# Blend_V2_0_20170309.net
KiCad netlist of a schematic drawn in EAGLE
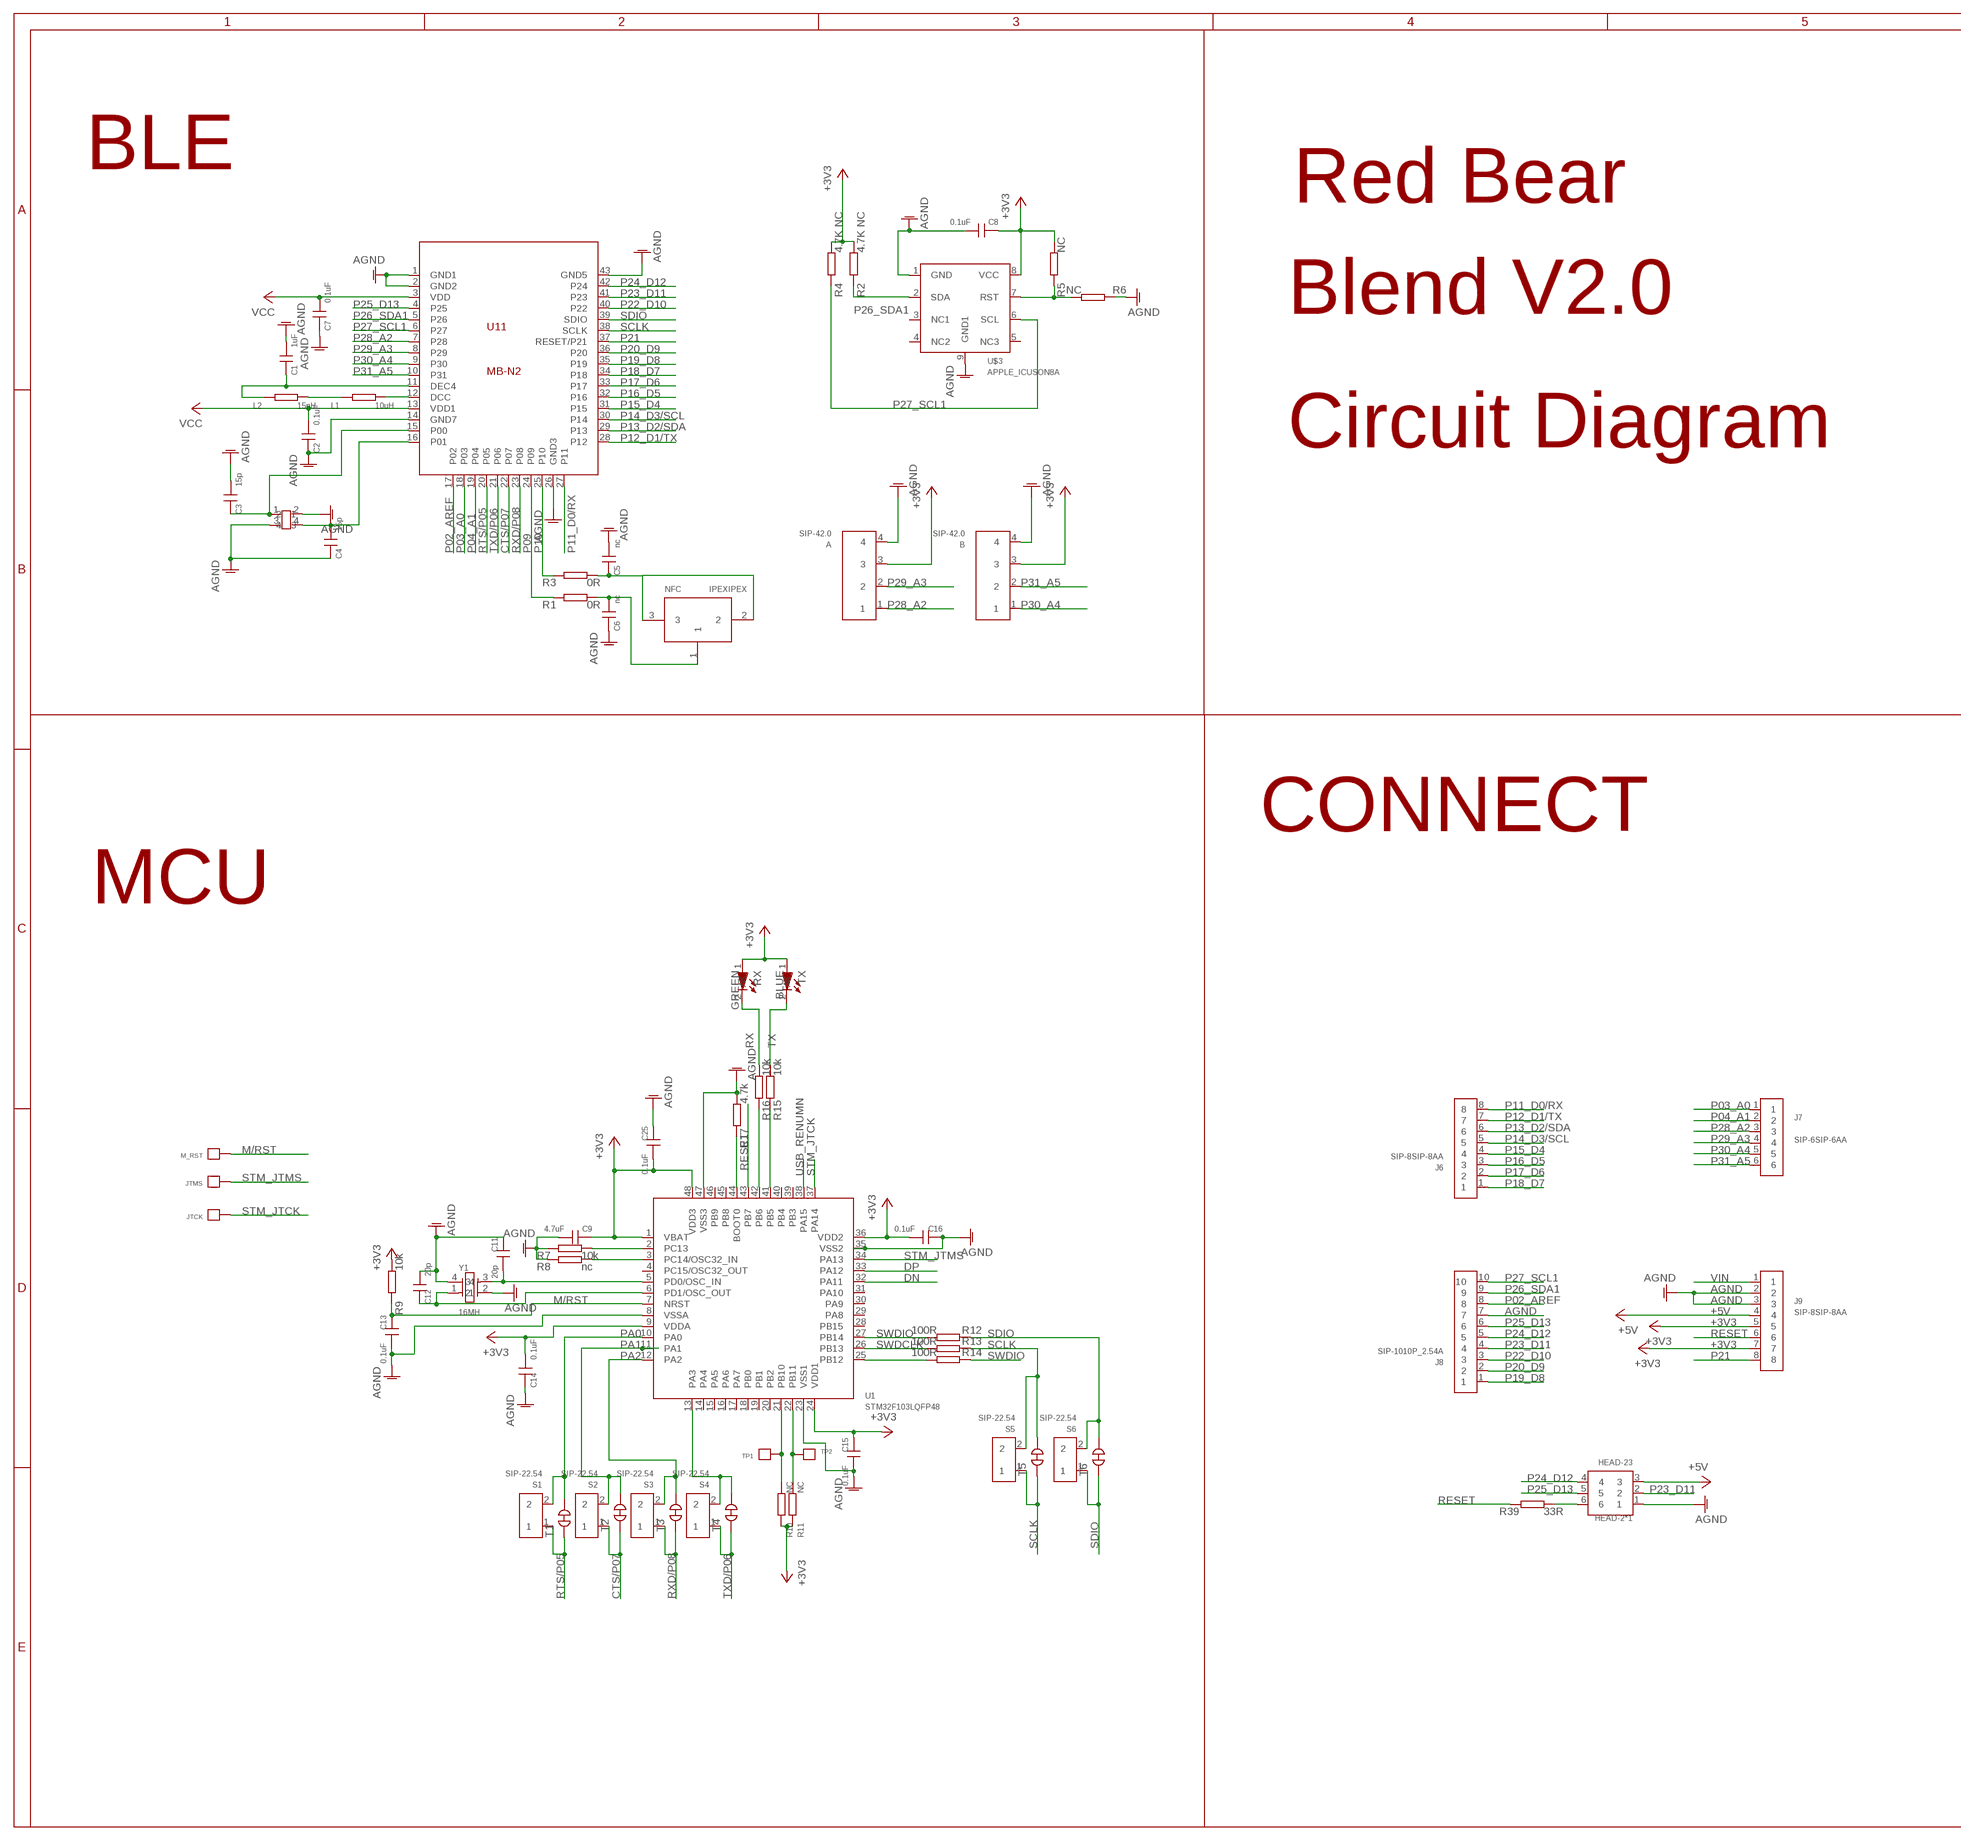
[diagram p0: schematic, sheet 1, part 1 of 2]
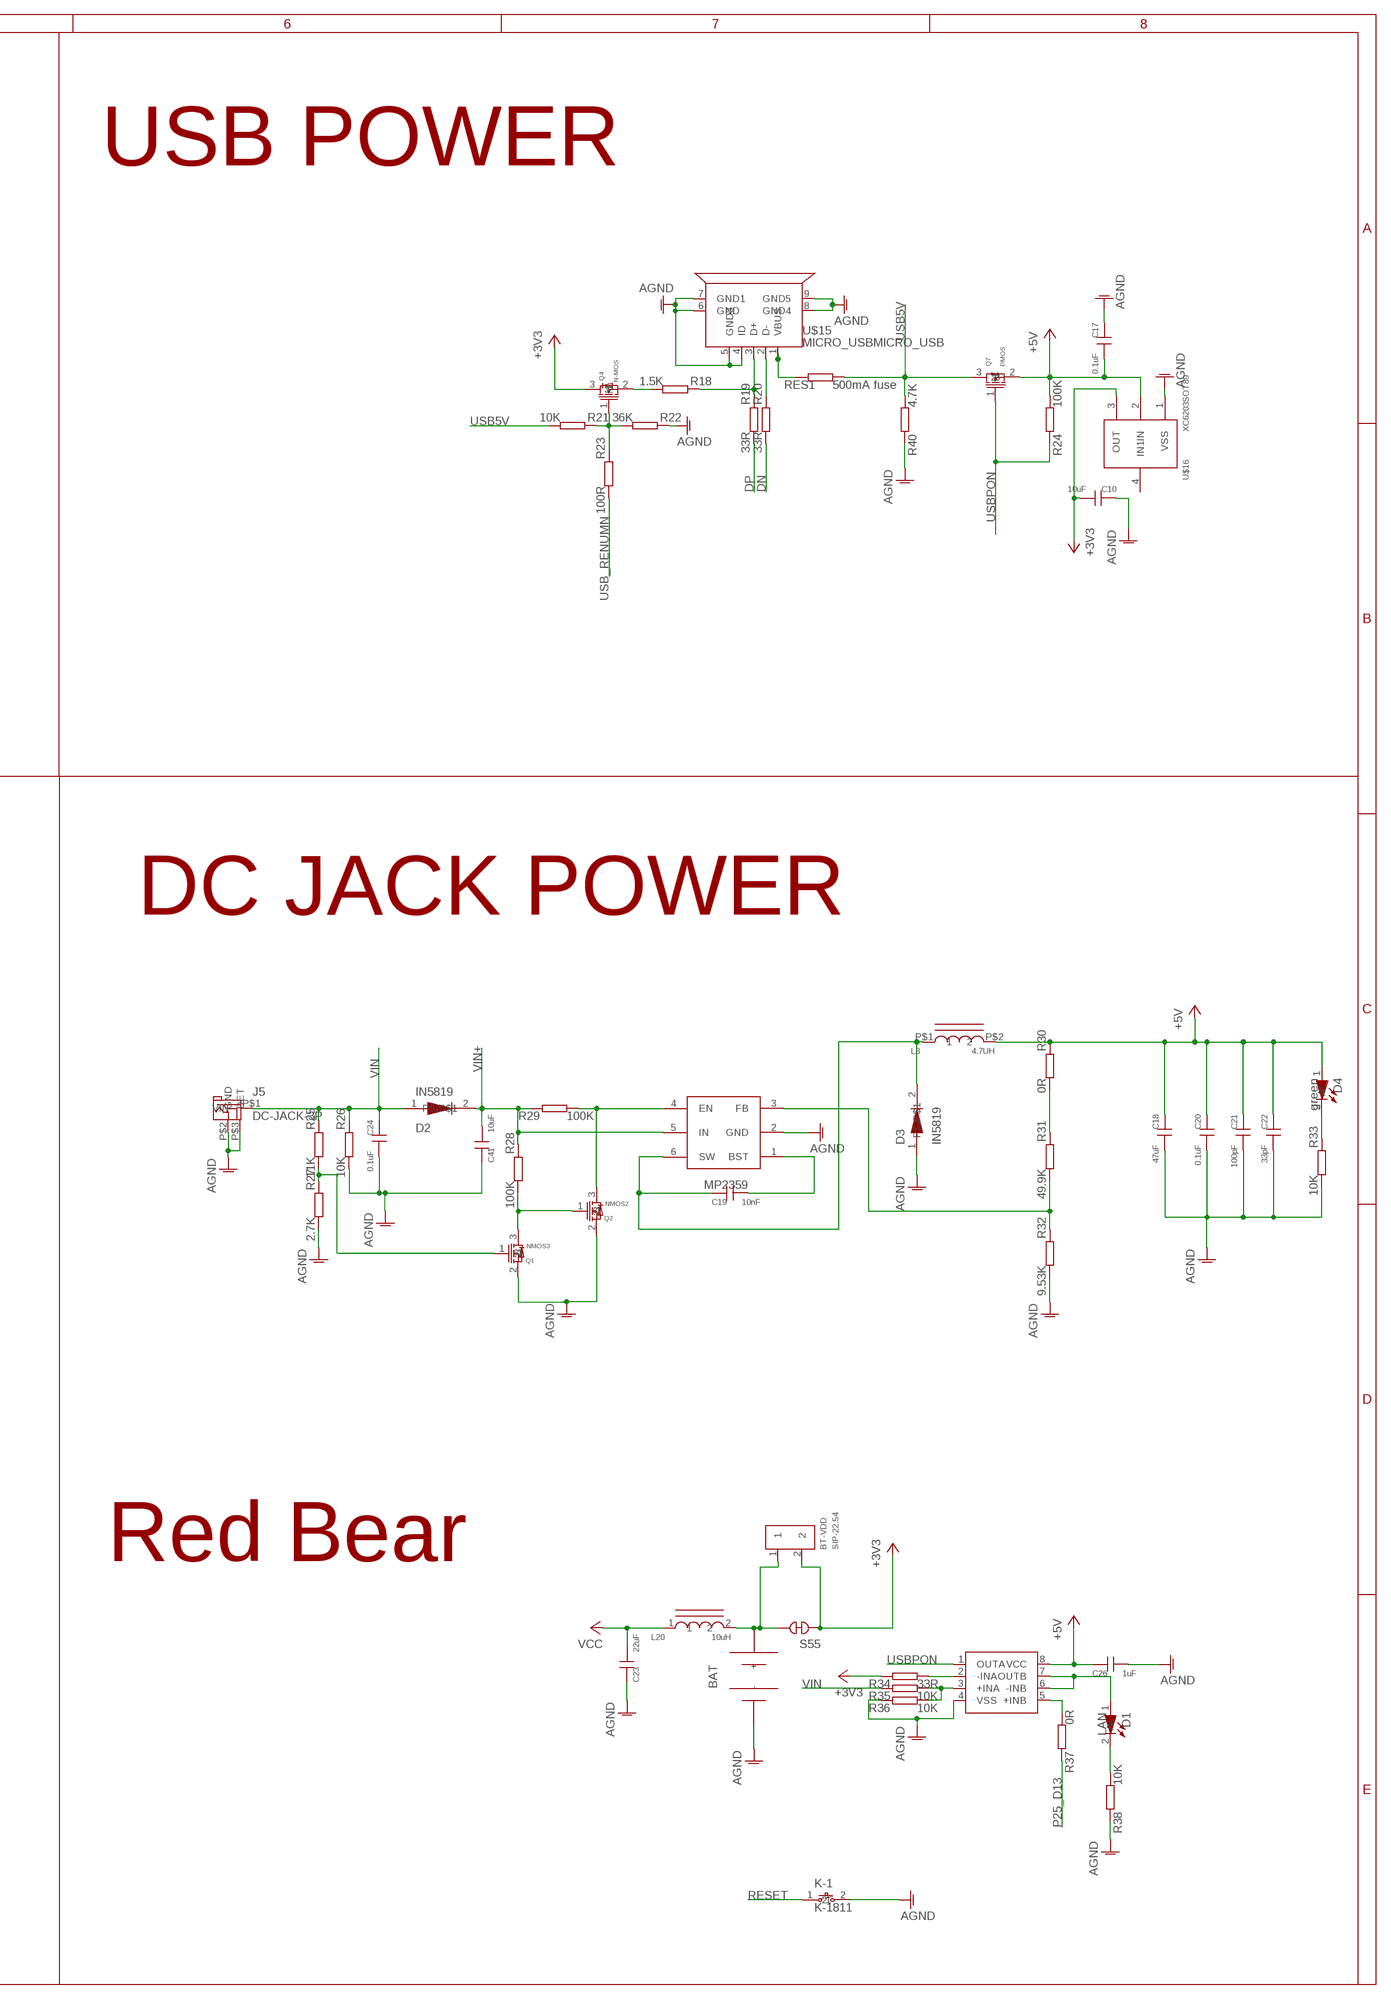
[diagram p1: schematic, sheet 1, part 2 of 2]

(export (version "E")
  (design (tool "Eeschema 10.0.6"))
  (components
    (comp (ref "A")
      (value "SIP-42.0")
      (footprint "eagle-import:CONETER-4-2.0")
      (libsource (lib "eagle-import") (part "SIP-42.0"))
    )
    (comp (ref "B")
      (value "SIP-42.0")
      (footprint "eagle-import:CONETER-4-2.0")
      (libsource (lib "eagle-import") (part "SIP-42.0"))
    )
    (comp (ref "BAT")
      (value "BAT")
      (footprint "eagle-import:BAT")
      (libsource (lib "eagle-import") (part "BAT"))
    )
    (comp (ref "BT-VDD")
      (value "SIP-22.54")
      (footprint "eagle-import:SIP-2")
      (libsource (lib "eagle-import") (part "SIP-22.54"))
    )
    (comp (ref "C1")
      (value "1uF")
      (footprint "eagle-import:C-0402")
      (libsource (lib "eagle-import") (part "CAP0402"))
    )
    (comp (ref "C2")
      (value "0.1uF")
      (footprint "eagle-import:C-0402")
      (libsource (lib "eagle-import") (part "CAP0402"))
    )
    (comp (ref "C3")
      (value "15p")
      (footprint "eagle-import:C-0402")
      (libsource (lib "eagle-import") (part "CAP0402"))
    )
    (comp (ref "C4")
      (value "15p")
      (footprint "eagle-import:C-0402")
      (libsource (lib "eagle-import") (part "CAP0402"))
    )
    (comp (ref "C5")
      (value "nc")
      (footprint "eagle-import:C-0402")
      (libsource (lib "eagle-import") (part "CAP0402"))
    )
    (comp (ref "C6")
      (value "nc")
      (footprint "eagle-import:C-0402")
      (libsource (lib "eagle-import") (part "CAP0402"))
    )
    (comp (ref "C7")
      (value "0.1uF")
      (footprint "eagle-import:C-0402")
      (libsource (lib "eagle-import") (part "CAP0402"))
    )
    (comp (ref "C8")
      (value "0.1uF")
      (footprint "eagle-import:C-0402")
      (libsource (lib "eagle-import") (part "CAP0402"))
    )
    (comp (ref "C9")
      (value "4.7uF")
      (footprint "eagle-import:C-0402")
      (libsource (lib "eagle-import") (part "CAP0402"))
    )
    (comp (ref "C10")
      (value "10uF")
      (footprint "eagle-import:C0805")
      (libsource (lib "eagle-import") (part "RedBeard_CAPC0805"))
    )
    (comp (ref "C11")
      (value "20p")
      (footprint "eagle-import:C-0402")
      (libsource (lib "eagle-import") (part "CAP0402"))
    )
    (comp (ref "C12")
      (value "20p")
      (footprint "eagle-import:C-0402")
      (libsource (lib "eagle-import") (part "CAP0402"))
    )
    (comp (ref "C13")
      (value "0.1uF")
      (footprint "eagle-import:C-0402")
      (libsource (lib "eagle-import") (part "CAP0402"))
    )
    (comp (ref "C14")
      (value "0.1uF")
      (footprint "eagle-import:C-0402")
      (libsource (lib "eagle-import") (part "CAP0402"))
    )
    (comp (ref "C15")
      (value "0.1uF")
      (footprint "eagle-import:C-0402")
      (libsource (lib "eagle-import") (part "CAP0402"))
    )
    (comp (ref "C16")
      (value "0.1uF")
      (footprint "eagle-import:C-0402")
      (libsource (lib "eagle-import") (part "CAP0402"))
    )
    (comp (ref "C17")
      (value "0.1uF")
      (footprint "eagle-import:C-0402")
      (libsource (lib "eagle-import") (part "CAP0402"))
    )
    (comp (ref "C18")
      (value "47uF")
      (footprint "eagle-import:C1206")
      (libsource (lib "eagle-import") (part "RedBeard_CAPC1206"))
    )
    (comp (ref "C19")
      (value "10nF")
      (footprint "eagle-import:C-0402")
      (libsource (lib "eagle-import") (part "CAP0402"))
    )
    (comp (ref "C20")
      (value "0.1uF")
      (footprint "eagle-import:C-0402")
      (libsource (lib "eagle-import") (part "CAP0402"))
    )
    (comp (ref "C21")
      (value "100pF")
      (footprint "eagle-import:C-0402")
      (libsource (lib "eagle-import") (part "CAP0402"))
    )
    (comp (ref "C22")
      (value "33pF")
      (footprint "eagle-import:C-0402")
      (libsource (lib "eagle-import") (part "CAP0402"))
    )
    (comp (ref "C23")
      (value "22uF")
      (footprint "eagle-import:C0805")
      (libsource (lib "eagle-import") (part "RedBeard_CAPC0805"))
    )
    (comp (ref "C24")
      (value "0.1uF")
      (footprint "eagle-import:C-0402")
      (libsource (lib "eagle-import") (part "CAP0402"))
    )
    (comp (ref "C25")
      (value "0.1uF")
      (footprint "eagle-import:C-0402")
      (libsource (lib "eagle-import") (part "CAP0402"))
    )
    (comp (ref "C26")
      (value "1uF")
      (footprint "eagle-import:C-0402")
      (libsource (lib "eagle-import") (part "CAP0402"))
    )
    (comp (ref "C41")
      (value "10uF")
      (footprint "eagle-import:C1206")
      (libsource (lib "eagle-import") (part "RedBeard_CAPC1206"))
    )
    (comp (ref "D1")
      (value "LAN")
      (footprint "eagle-import:LED-0603")
      (libsource (lib "eagle-import") (part "LEDLED-0603"))
    )
    (comp (ref "D3")
      (value "IN5819")
      (footprint "eagle-import:D-1810")
      (libsource (lib "eagle-import") (part "DIODED-1810"))
    )
    (comp (ref "D4")
      (value "green")
      (footprint "eagle-import:LED-0603")
      (libsource (lib "eagle-import") (part "LEDLED-0603"))
    )
    (comp (ref "HEAD-2*1")
      (value "HEAD-23")
      (footprint "eagle-import:PAIZHEN3X2PIN2.54")
      (libsource (lib "eagle-import") (part "HEAD-23"))
    )
    (comp (ref "IN5819")
      (value "D2")
      (footprint "eagle-import:D-1810")
      (libsource (lib "eagle-import") (part "DIODED-1810"))
    )
    (comp (ref "J5")
      (value "DC-JACK-3P")
      (footprint "eagle-import:DC-005")
      (libsource (lib "eagle-import") (part "DC-005DC-005"))
    )
    (comp (ref "J6")
      (value "SIP-8SIP-8AA")
      (footprint "eagle-import:PAIZHEN8P_2.54AA")
      (libsource (lib "eagle-import") (part "SIP-8SIP-8AA"))
    )
    (comp (ref "J7")
      (value "SIP-6SIP-6AA")
      (footprint "eagle-import:PAIZHEN6P_2.54AA")
      (libsource (lib "eagle-import") (part "SIP-6SIP-6AA"))
    )
    (comp (ref "J8")
      (value "SIP-1010P_2.54A")
      (footprint "eagle-import:PAIZHEN10P-2.54A")
      (libsource (lib "eagle-import") (part "SIP-1010P_2.54A"))
    )
    (comp (ref "J9")
      (value "SIP-8SIP-8AA")
      (footprint "eagle-import:PAIZHEN8P_2.54AA")
      (libsource (lib "eagle-import") (part "SIP-8SIP-8AA"))
    )
    (comp (ref "JTCK")
      (value "TPTP")
      (footprint "eagle-import:TP")
      (libsource (lib "eagle-import") (part "TPTP"))
    )
    (comp (ref "JTMS")
      (value "TPTP")
      (footprint "eagle-import:TP")
      (libsource (lib "eagle-import") (part "TPTP"))
    )
    (comp (ref "K-1")
      (value "K-1811")
      (footprint "eagle-import:K2-1101F")
      (libsource (lib "eagle-import") (part "K-1811"))
    )
    (comp (ref "L1")
      (value "10uH")
      (footprint "eagle-import:R0603")
      (libsource (lib "eagle-import") (part "RESR0603"))
    )
    (comp (ref "L2")
      (value "15nH")
      (footprint "eagle-import:R-0402S")
      (libsource (lib "eagle-import") (part "RES0402S"))
    )
    (comp (ref "L3")
      (value "4.7UH")
      (footprint "eagle-import:L4X4")
      (libsource (lib "eagle-import") (part "LL4X4"))
    )
    (comp (ref "L20")
      (value "10uH")
      (footprint "eagle-import:R-0603A")
      (libsource (lib "eagle-import") (part "L"))
    )
    (comp (ref "MP2359")
      (value "MP2359")
      (footprint "eagle-import:MP2359")
      (libsource (lib "eagle-import") (part "MP2359"))
    )
    (comp (ref "M_RST")
      (value "TPTP")
      (footprint "eagle-import:TP")
      (libsource (lib "eagle-import") (part "TPTP"))
    )
    (comp (ref "NFC")
      (value "IPEXIPEX")
      (footprint "eagle-import:IPEX")
      (libsource (lib "eagle-import") (part "IPEXIPEX"))
    )
    (comp (ref "NMOS2")
      (value "Q2")
      (footprint "eagle-import:SOT-23")
      (libsource (lib "eagle-import") (part "NMOSSOT-23"))
    )
    (comp (ref "NMOS3")
      (value "Q1")
      (footprint "eagle-import:SOT-23")
      (libsource (lib "eagle-import") (part "NMOSSOT-23"))
    )
    (comp (ref "Q4")
      (value "N-MOS")
      (footprint "eagle-import:SOT-23")
      (libsource (lib "eagle-import") (part "NMOSSOT-23"))
    )
    (comp (ref "Q7")
      (value "PMOS")
      (footprint "eagle-import:SOT-23")
      (libsource (lib "eagle-import") (part "PMOS"))
    )
    (comp (ref "R1")
      (value "0R")
      (footprint "eagle-import:R0402")
      (libsource (lib "eagle-import") (part "RedBeard_RESR0402"))
    )
    (comp (ref "R2")
      (value "4.7K NC")
      (footprint "eagle-import:R0402")
      (libsource (lib "eagle-import") (part "RedBeard_RESR0402"))
    )
    (comp (ref "R3")
      (value "0R")
      (footprint "eagle-import:R0402")
      (libsource (lib "eagle-import") (part "RedBeard_RESR0402"))
    )
    (comp (ref "R4")
      (value "4.7K NC")
      (footprint "eagle-import:R0402")
      (libsource (lib "eagle-import") (part "RedBeard_RESR0402"))
    )
    (comp (ref "R5")
      (value "NC")
      (footprint "eagle-import:R0402")
      (libsource (lib "eagle-import") (part "RedBeard_RESR0402"))
    )
    (comp (ref "R6")
      (value "NC")
      (footprint "eagle-import:R0402")
      (libsource (lib "eagle-import") (part "RedBeard_RESR0402"))
    )
    (comp (ref "R7")
      (value "10k")
      (footprint "eagle-import:R0402")
      (libsource (lib "eagle-import") (part "RedBeard_RESR0402"))
    )
    (comp (ref "R8")
      (value "nc")
      (footprint "eagle-import:R0402")
      (libsource (lib "eagle-import") (part "RedBeard_RESR0402"))
    )
    (comp (ref "R9")
      (value "10k")
      (footprint "eagle-import:R0402")
      (libsource (lib "eagle-import") (part "RedBeard_RESR0402"))
    )
    (comp (ref "R10")
      (value "NC")
      (footprint "eagle-import:R0603")
      (libsource (lib "eagle-import") (part "RESR0603"))
    )
    (comp (ref "R11")
      (value "NC")
      (footprint "eagle-import:R0603")
      (libsource (lib "eagle-import") (part "RESR0603"))
    )
    (comp (ref "R12")
      (value "100R")
      (footprint "eagle-import:R0402")
      (libsource (lib "eagle-import") (part "RedBeard_RESR0402"))
    )
    (comp (ref "R13")
      (value "100R")
      (footprint "eagle-import:R0402")
      (libsource (lib "eagle-import") (part "RedBeard_RESR0402"))
    )
    (comp (ref "R14")
      (value "100R")
      (footprint "eagle-import:R0402")
      (libsource (lib "eagle-import") (part "RedBeard_RESR0402"))
    )
    (comp (ref "R15")
      (value "10k")
      (footprint "eagle-import:R0402")
      (libsource (lib "eagle-import") (part "RedBeard_RESR0402"))
    )
    (comp (ref "R16")
      (value "10k")
      (footprint "eagle-import:R0402")
      (libsource (lib "eagle-import") (part "RedBeard_RESR0402"))
    )
    (comp (ref "R17")
      (value "4.7k")
      (footprint "eagle-import:R0402")
      (libsource (lib "eagle-import") (part "RedBeard_RESR0402"))
    )
    (comp (ref "R18")
      (value "1.5K")
      (footprint "eagle-import:R0402")
      (libsource (lib "eagle-import") (part "RedBeard_RESR0402"))
    )
    (comp (ref "R19")
      (value "33R")
      (footprint "eagle-import:R0402")
      (libsource (lib "eagle-import") (part "RedBeard_RESR0402"))
    )
    (comp (ref "R20")
      (value "33R")
      (footprint "eagle-import:R0402")
      (libsource (lib "eagle-import") (part "RedBeard_RESR0402"))
    )
    (comp (ref "R21")
      (value "10K")
      (footprint "eagle-import:R0402")
      (libsource (lib "eagle-import") (part "RedBeard_RESR0402"))
    )
    (comp (ref "R22")
      (value "36K")
      (footprint "eagle-import:R0402")
      (libsource (lib "eagle-import") (part "RedBeard_RESR0402"))
    )
    (comp (ref "R23")
      (value "100R")
      (footprint "eagle-import:R0402")
      (libsource (lib "eagle-import") (part "RedBeard_RESR0402"))
    )
    (comp (ref "R24")
      (value "100K")
      (footprint "eagle-import:R0402")
      (libsource (lib "eagle-import") (part "RedBeard_RESR0402"))
    )
    (comp (ref "R25")
      (value "11K")
      (footprint "eagle-import:R0402")
      (libsource (lib "eagle-import") (part "RedBeard_RESR0402"))
    )
    (comp (ref "R26")
      (value "10K")
      (footprint "eagle-import:R0402")
      (libsource (lib "eagle-import") (part "RedBeard_RESR0402"))
    )
    (comp (ref "R27")
      (value "2.7K")
      (footprint "eagle-import:R0402")
      (libsource (lib "eagle-import") (part "RedBeard_RESR0402"))
    )
    (comp (ref "R28")
      (value "100K")
      (footprint "eagle-import:R0402")
      (libsource (lib "eagle-import") (part "RedBeard_RESR0402"))
    )
    (comp (ref "R29")
      (value "100K")
      (footprint "eagle-import:R0402")
      (libsource (lib "eagle-import") (part "RedBeard_RESR0402"))
    )
    (comp (ref "R30")
      (value "0R")
      (footprint "eagle-import:R0402")
      (libsource (lib "eagle-import") (part "RedBeard_RESR0402"))
    )
    (comp (ref "R31")
      (value "49.9K")
      (footprint "eagle-import:R0402")
      (libsource (lib "eagle-import") (part "RedBeard_RESR0402"))
    )
    (comp (ref "R32")
      (value "9.53K")
      (footprint "eagle-import:R0402")
      (libsource (lib "eagle-import") (part "RedBeard_RESR0402"))
    )
    (comp (ref "R33")
      (value "10K")
      (footprint "eagle-import:R0402")
      (libsource (lib "eagle-import") (part "RedBeard_RESR0402"))
    )
    (comp (ref "R34")
      (value "33R")
      (footprint "eagle-import:R0402")
      (libsource (lib "eagle-import") (part "RedBeard_RESR0402"))
    )
    (comp (ref "R35")
      (value "10K")
      (footprint "eagle-import:R0402")
      (libsource (lib "eagle-import") (part "RedBeard_RESR0402"))
    )
    (comp (ref "R36")
      (value "10K")
      (footprint "eagle-import:R0402")
      (libsource (lib "eagle-import") (part "RedBeard_RESR0402"))
    )
    (comp (ref "R37")
      (value "0R")
      (footprint "eagle-import:R0402")
      (libsource (lib "eagle-import") (part "RedBeard_RESR0402"))
    )
    (comp (ref "R38")
      (value "10K")
      (footprint "eagle-import:R0402")
      (libsource (lib "eagle-import") (part "RedBeard_RESR0402"))
    )
    (comp (ref "R39")
      (value "33R")
      (footprint "eagle-import:R0402")
      (libsource (lib "eagle-import") (part "RedBeard_RESR0402"))
    )
    (comp (ref "R40")
      (value "4.7K")
      (footprint "eagle-import:R0402")
      (libsource (lib "eagle-import") (part "RedBeard_RESR0402"))
    )
    (comp (ref "RES1")
      (value "500mA fuse")
      (footprint "eagle-import:R1206A")
      (libsource (lib "eagle-import") (part "RedBeard_RES"))
    )
    (comp (ref "RX")
      (value "GREEN")
      (footprint "eagle-import:LED0603")
      (libsource (lib "eagle-import") (part "LED"))
    )
    (comp (ref "S1")
      (value "SIP-22.54")
      (footprint "eagle-import:SIP-2")
      (libsource (lib "eagle-import") (part "SIP-22.54"))
    )
    (comp (ref "S2")
      (value "SIP-22.54")
      (footprint "eagle-import:SIP-2")
      (libsource (lib "eagle-import") (part "SIP-22.54"))
    )
    (comp (ref "S3")
      (value "SIP-22.54")
      (footprint "eagle-import:SIP-2")
      (libsource (lib "eagle-import") (part "SIP-22.54"))
    )
    (comp (ref "S4")
      (value "SIP-22.54")
      (footprint "eagle-import:SIP-2")
      (libsource (lib "eagle-import") (part "SIP-22.54"))
    )
    (comp (ref "S5")
      (value "SIP-22.54")
      (footprint "eagle-import:SIP-2")
      (libsource (lib "eagle-import") (part "SIP-22.54"))
    )
    (comp (ref "S6")
      (value "SIP-22.54")
      (footprint "eagle-import:SIP-2")
      (libsource (lib "eagle-import") (part "SIP-22.54"))
    )
    (comp (ref "S55")
      (value "TP_OPEN")
      (footprint "eagle-import:TP_OPEN")
      (libsource (lib "eagle-import") (part "TP_OPEN"))
    )
    (comp (ref "T1")
      (value "TP_OPEN")
      (footprint "eagle-import:TP_OPEN")
      (libsource (lib "eagle-import") (part "TP_OPEN"))
    )
    (comp (ref "T2")
      (value "TP_OPEN")
      (footprint "eagle-import:TP_OPEN")
      (libsource (lib "eagle-import") (part "TP_OPEN"))
    )
    (comp (ref "T3")
      (value "TP_OPEN")
      (footprint "eagle-import:TP_OPEN")
      (libsource (lib "eagle-import") (part "TP_OPEN"))
    )
    (comp (ref "T4")
      (value "TP_OPEN")
      (footprint "eagle-import:TP_OPEN")
      (libsource (lib "eagle-import") (part "TP_OPEN"))
    )
    (comp (ref "T5")
      (value "TP_OPEN")
      (footprint "eagle-import:TP_OPEN")
      (libsource (lib "eagle-import") (part "TP_OPEN"))
    )
    (comp (ref "T6")
      (value "TP_OPEN")
      (footprint "eagle-import:TP_OPEN")
      (libsource (lib "eagle-import") (part "TP_OPEN"))
    )
    (comp (ref "TP1")
      (value "TPTP")
      (footprint "eagle-import:TP")
      (libsource (lib "eagle-import") (part "TPTP"))
    )
    (comp (ref "TP2")
      (value "TPTP")
      (footprint "eagle-import:TP")
      (libsource (lib "eagle-import") (part "TPTP"))
    )
    (comp (ref "TX")
      (value "BLUE")
      (footprint "eagle-import:LED0603")
      (libsource (lib "eagle-import") (part "LED"))
    )
    (comp (ref "U$2")
      (value "CRY_7015")
      (footprint "eagle-import:CRY_7015_SMT")
      (libsource (lib "eagle-import") (part "CRY_7015"))
    )
    (comp (ref "U$3")
      (value "APPLE_ICUSON8A")
      (footprint "eagle-import:USON8_A")
      (libsource (lib "eagle-import") (part "APPLE_ICUSON8A"))
    )
    (comp (ref "U$15")
      (value "MICRO_USBMICRO_USB")
      (footprint "eagle-import:MICRO_USB")
      (libsource (lib "eagle-import") (part "MICRO_USBMICRO_USB"))
    )
    (comp (ref "U$16")
      (value "XC6203SOT89")
      (footprint "eagle-import:SOT-89")
      (libsource (lib "eagle-import") (part "XC6203SOT89"))
    )
    (comp (ref "U$19")
      (value "SGM358")
      (footprint "eagle-import:SOP-8")
      (libsource (lib "eagle-import") (part "SGM358"))
    )
    (comp (ref "U1")
      (value "STM32F103LQFP48")
      (footprint "eagle-import:LQFP-48-7X7")
      (libsource (lib "eagle-import") (part "STM32F103LQFP48"))
    )
    (comp (ref "U11")
      (value "MB-N2")
      (footprint "eagle-import:RBT07")
      (libsource (lib "eagle-import") (part "RBT07"))
    )
    (comp (ref "Y1")
      (value "16MH")
      (footprint "eagle-import:CRY_3225_SMT")
      (libsource (lib "eagle-import") (part "CRY3225"))
    )
  )
  (nets
    (net (code "1") (name "+3V3") (class "Default")
      (node (ref "A") (pin "3") (pinfunction "3_3") (pintype "bidirectional"))
      (node (ref "B") (pin "3") (pinfunction "3_3") (pintype "bidirectional"))
      (node (ref "BT-VDD") (pin "2") (pinfunction "2_2") (pintype "bidirectional"))
      (node (ref "C10") (pin "1") (pinfunction "1_1") (pintype "bidirectional"))
      (node (ref "C14") (pin "1") (pinfunction "1_1") (pintype "bidirectional"))
      (node (ref "C15") (pin "2") (pinfunction "2_2") (pintype "bidirectional"))
      (node (ref "C16") (pin "1") (pinfunction "1_1") (pintype "bidirectional"))
      (node (ref "C25") (pin "1") (pinfunction "1_1") (pintype "bidirectional"))
      (node (ref "C8") (pin "2") (pinfunction "2_2") (pintype "bidirectional"))
      (node (ref "C9") (pin "2") (pinfunction "2_2") (pintype "bidirectional"))
      (node (ref "J9") (pin "5") (pinfunction "5_5") (pintype "bidirectional"))
      (node (ref "J9") (pin "7") (pinfunction "7_7") (pintype "bidirectional"))
      (node (ref "Q4") (pin "3") (pinfunction "2_3") (pintype "bidirectional"))
      (node (ref "R10") (pin "1") (pinfunction "1_1") (pintype "bidirectional"))
      (node (ref "R11") (pin "1") (pinfunction "1_1") (pintype "bidirectional"))
      (node (ref "R2") (pin "2") (pinfunction "2_2") (pintype "bidirectional"))
      (node (ref "R34") (pin "1") (pinfunction "1_1") (pintype "bidirectional"))
      (node (ref "R4") (pin "2") (pinfunction "2_2") (pintype "bidirectional"))
      (node (ref "R5") (pin "2") (pinfunction "2_2") (pintype "bidirectional"))
      (node (ref "R9") (pin "2") (pinfunction "2_2") (pintype "bidirectional"))
      (node (ref "RX") (pin "1") (pinfunction "A_1") (pintype "bidirectional"))
      (node (ref "S55") (pin "P$2") (pinfunction "P$2_P$2") (pintype "bidirectional"))
      (node (ref "TX") (pin "1") (pinfunction "A_1") (pintype "bidirectional"))
      (node (ref "U$16") (pin "3") (pinfunction "OUT_3") (pintype "power_in"))
      (node (ref "U$3") (pin "8") (pinfunction "VCC_8") (pintype "bidirectional"))
      (node (ref "U1") (pin "1") (pinfunction "VBAT_1") (pintype "bidirectional"))
      (node (ref "U1") (pin "24") (pinfunction "VDD1_24") (pintype "bidirectional"))
      (node (ref "U1") (pin "36") (pinfunction "VDD2_36") (pintype "bidirectional"))
      (node (ref "U1") (pin "48") (pinfunction "VDD3_48") (pintype "bidirectional"))
      (node (ref "U1") (pin "9") (pinfunction "VDDA_9") (pintype "bidirectional"))
    )
    (net (code "2") (name "+5V") (class "Default")
      (node (ref "C17") (pin "1") (pinfunction "1_1") (pintype "bidirectional"))
      (node (ref "C18") (pin "2") (pinfunction "2_2") (pintype "bidirectional"))
      (node (ref "C20") (pin "2") (pinfunction "2_2") (pintype "bidirectional"))
      (node (ref "C21") (pin "2") (pinfunction "2_2") (pintype "bidirectional"))
      (node (ref "C22") (pin "2") (pinfunction "2_2") (pintype "bidirectional"))
      (node (ref "C26") (pin "2") (pinfunction "2_2") (pintype "bidirectional"))
      (node (ref "D4") (pin "1") (pinfunction "A_1") (pintype "bidirectional"))
      (node (ref "HEAD-2*1") (pin "3") (pinfunction "3_3") (pintype "bidirectional"))
      (node (ref "J9") (pin "4") (pinfunction "4_4") (pintype "bidirectional"))
      (node (ref "L3") (pin "P$2") (pinfunction "2_P$2") (pintype "bidirectional"))
      (node (ref "Q7") (pin "2") (pinfunction "2_2") (pintype "bidirectional"))
      (node (ref "R24") (pin "2") (pinfunction "2_2") (pintype "bidirectional"))
      (node (ref "R30") (pin "1") (pinfunction "1_1") (pintype "bidirectional"))
      (node (ref "U$16") (pin "2") (pinfunction "IN_2") (pintype "bidirectional"))
      (node (ref "U$19") (pin "8") (pinfunction "VCC_8") (pintype "bidirectional"))
    )
    (net (code "3") (name "/CTS{slash}P07") (class "Default")
      (node (ref "S2") (pin "1") (pinfunction "1_1") (pintype "bidirectional"))
      (node (ref "T2") (pin "P$2") (pinfunction "P$2_P$2") (pintype "bidirectional"))
      (node (ref "U11") (pin "22") (pinfunction "P07_22") (pintype "bidirectional"))
    )
    (net (code "4") (name "/DN") (class "Default")
      (node (ref "R20") (pin "2") (pinfunction "2_2") (pintype "bidirectional"))
      (node (ref "U1") (pin "32") (pinfunction "PA11_32") (pintype "bidirectional"))
    )
    (net (code "5") (name "/DP") (class "Default")
      (node (ref "R19") (pin "2") (pinfunction "2_2") (pintype "bidirectional"))
      (node (ref "U1") (pin "33") (pinfunction "PA12_33") (pintype "bidirectional"))
    )
    (net (code "6") (name "/IN1") (class "Default")
      (node (ref "U$16") (pin "4") (pinfunction "IN1_4") (pintype "power_in"))
    )
    (net (code "7") (name "/M{slash}RST") (class "Default")
      (node (ref "C13") (pin "2") (pinfunction "2_2") (pintype "bidirectional"))
      (node (ref "M_RST") (pin "P$1") (pinfunction "1_P$1") (pintype "bidirectional"))
      (node (ref "R9") (pin "1") (pinfunction "1_1") (pintype "bidirectional"))
      (node (ref "U1") (pin "7") (pinfunction "NRST_7") (pintype "bidirectional"))
    )
    (net (code "8") (name "/P02_AREF") (class "Default")
      (node (ref "J8") (pin "8") (pinfunction "8_8") (pintype "bidirectional"))
      (node (ref "U11") (pin "17") (pinfunction "P02_17") (pintype "bidirectional"))
    )
    (net (code "9") (name "/P03_A0") (class "Default")
      (node (ref "J7") (pin "1") (pinfunction "1_1") (pintype "bidirectional"))
      (node (ref "U11") (pin "18") (pinfunction "P03_18") (pintype "bidirectional"))
    )
    (net (code "10") (name "/P04_A1") (class "Default")
      (node (ref "J7") (pin "2") (pinfunction "2_2") (pintype "bidirectional"))
      (node (ref "U11") (pin "19") (pinfunction "P04_19") (pintype "bidirectional"))
    )
    (net (code "11") (name "/P09") (class "Default")
      (node (ref "R1") (pin "1") (pinfunction "1_1") (pintype "bidirectional"))
      (node (ref "U11") (pin "24") (pinfunction "P09_24") (pintype "bidirectional"))
    )
    (net (code "12") (name "/P10") (class "Default")
      (node (ref "R3") (pin "1") (pinfunction "1_1") (pintype "bidirectional"))
      (node (ref "U11") (pin "25") (pinfunction "P10_25") (pintype "bidirectional"))
    )
    (net (code "13") (name "/P11_D0{slash}RX") (class "Default")
      (node (ref "J6") (pin "8") (pinfunction "8_8") (pintype "bidirectional"))
      (node (ref "U11") (pin "27") (pinfunction "P11_27") (pintype "bidirectional"))
    )
    (net (code "14") (name "/P12_D1{slash}TX") (class "Default")
      (node (ref "J6") (pin "7") (pinfunction "7_7") (pintype "bidirectional"))
      (node (ref "U11") (pin "28") (pinfunction "P12_28") (pintype "bidirectional"))
    )
    (net (code "15") (name "/P13_D2{slash}SDA") (class "Default")
      (node (ref "J6") (pin "6") (pinfunction "6_6") (pintype "bidirectional"))
      (node (ref "U11") (pin "29") (pinfunction "P13_29") (pintype "bidirectional"))
    )
    (net (code "16") (name "/P14_D3{slash}SCL") (class "Default")
      (node (ref "J6") (pin "5") (pinfunction "5_5") (pintype "bidirectional"))
      (node (ref "U11") (pin "30") (pinfunction "P14_30") (pintype "bidirectional"))
    )
    (net (code "17") (name "/P15_D4") (class "Default")
      (node (ref "J6") (pin "4") (pinfunction "4_4") (pintype "bidirectional"))
      (node (ref "U11") (pin "31") (pinfunction "P15_31") (pintype "bidirectional"))
    )
    (net (code "18") (name "/P16_D5") (class "Default")
      (node (ref "J6") (pin "3") (pinfunction "3_3") (pintype "bidirectional"))
      (node (ref "U11") (pin "32") (pinfunction "P16_32") (pintype "bidirectional"))
    )
    (net (code "19") (name "/P17_D6") (class "Default")
      (node (ref "J6") (pin "2") (pinfunction "2_2") (pintype "bidirectional"))
      (node (ref "U11") (pin "33") (pinfunction "P17_33") (pintype "bidirectional"))
    )
    (net (code "20") (name "/P18_D7") (class "Default")
      (node (ref "J6") (pin "1") (pinfunction "1_1") (pintype "bidirectional"))
      (node (ref "U11") (pin "34") (pinfunction "P18_34") (pintype "bidirectional"))
    )
    (net (code "21") (name "/P19_D8") (class "Default")
      (node (ref "J8") (pin "1") (pinfunction "1_1") (pintype "bidirectional"))
      (node (ref "U11") (pin "35") (pinfunction "P19_35") (pintype "bidirectional"))
    )
    (net (code "22") (name "/P20_D9") (class "Default")
      (node (ref "J8") (pin "2") (pinfunction "2_2") (pintype "bidirectional"))
      (node (ref "U11") (pin "36") (pinfunction "P20_36") (pintype "bidirectional"))
    )
    (net (code "23") (name "/P21") (class "Default")
      (node (ref "J9") (pin "8") (pinfunction "8_8") (pintype "bidirectional"))
      (node (ref "U11") (pin "37") (pinfunction "RESET/P21_37") (pintype "bidirectional"))
    )
    (net (code "24") (name "/P22_D10") (class "Default")
      (node (ref "J8") (pin "3") (pinfunction "3_3") (pintype "bidirectional"))
      (node (ref "U11") (pin "40") (pinfunction "P22_40") (pintype "bidirectional"))
    )
    (net (code "25") (name "/P23_D11") (class "Default")
      (node (ref "HEAD-2*1") (pin "2") (pinfunction "2_2") (pintype "bidirectional"))
      (node (ref "J8") (pin "4") (pinfunction "4_4") (pintype "bidirectional"))
      (node (ref "U11") (pin "41") (pinfunction "P23_41") (pintype "bidirectional"))
    )
    (net (code "26") (name "/P24_D12") (class "Default")
      (node (ref "HEAD-2*1") (pin "4") (pinfunction "4_4") (pintype "bidirectional"))
      (node (ref "J8") (pin "5") (pinfunction "5_5") (pintype "bidirectional"))
      (node (ref "U11") (pin "42") (pinfunction "P24_42") (pintype "bidirectional"))
    )
    (net (code "27") (name "/P25_D13") (class "Default")
      (node (ref "HEAD-2*1") (pin "5") (pinfunction "5_5") (pintype "bidirectional"))
      (node (ref "J8") (pin "6") (pinfunction "6_6") (pintype "bidirectional"))
      (node (ref "R37") (pin "1") (pinfunction "1_1") (pintype "bidirectional"))
      (node (ref "U11") (pin "4") (pinfunction "P25_4") (pintype "bidirectional"))
    )
    (net (code "28") (name "/P26_SDA1") (class "Default")
      (node (ref "J8") (pin "9") (pinfunction "9_9") (pintype "bidirectional"))
      (node (ref "R2") (pin "1") (pinfunction "1_1") (pintype "bidirectional"))
      (node (ref "U$3") (pin "2") (pinfunction "SDA_2") (pintype "bidirectional"))
      (node (ref "U11") (pin "5") (pinfunction "P26_5") (pintype "bidirectional"))
    )
    (net (code "29") (name "/P27_SCL1") (class "Default")
      (node (ref "J8") (pin "10") (pinfunction "10_10") (pintype "bidirectional"))
      (node (ref "R4") (pin "1") (pinfunction "1_1") (pintype "bidirectional"))
      (node (ref "U$3") (pin "6") (pinfunction "SCL_6") (pintype "bidirectional"))
      (node (ref "U11") (pin "6") (pinfunction "P27_6") (pintype "bidirectional"))
    )
    (net (code "30") (name "/P28_A2") (class "Default")
      (node (ref "A") (pin "1") (pinfunction "1_1") (pintype "bidirectional"))
      (node (ref "J7") (pin "3") (pinfunction "3_3") (pintype "bidirectional"))
      (node (ref "U11") (pin "7") (pinfunction "P28_7") (pintype "bidirectional"))
    )
    (net (code "31") (name "/P29_A3") (class "Default")
      (node (ref "A") (pin "2") (pinfunction "2_2") (pintype "bidirectional"))
      (node (ref "J7") (pin "4") (pinfunction "4_4") (pintype "bidirectional"))
      (node (ref "U11") (pin "8") (pinfunction "P29_8") (pintype "bidirectional"))
    )
    (net (code "32") (name "/P30_A4") (class "Default")
      (node (ref "B") (pin "1") (pinfunction "1_1") (pintype "bidirectional"))
      (node (ref "J7") (pin "5") (pinfunction "5_5") (pintype "bidirectional"))
      (node (ref "U11") (pin "9") (pinfunction "P30_9") (pintype "bidirectional"))
    )
    (net (code "33") (name "/P31_A5") (class "Default")
      (node (ref "B") (pin "2") (pinfunction "2_2") (pintype "bidirectional"))
      (node (ref "J7") (pin "6") (pinfunction "6_6") (pintype "bidirectional"))
      (node (ref "U11") (pin "10") (pinfunction "P31_10") (pintype "bidirectional"))
    )
    (net (code "34") (name "/PA0") (class "Default")
      (node (ref "S1") (pin "2") (pinfunction "2_2") (pintype "bidirectional"))
      (node (ref "T1") (pin "P$1") (pinfunction "P$1_P$1") (pintype "bidirectional"))
      (node (ref "U1") (pin "10") (pinfunction "PA0_10") (pintype "bidirectional"))
    )
    (net (code "35") (name "/PA1") (class "Default")
      (node (ref "S2") (pin "2") (pinfunction "2_2") (pintype "bidirectional"))
      (node (ref "T2") (pin "P$1") (pinfunction "P$1_P$1") (pintype "bidirectional"))
      (node (ref "U1") (pin "11") (pinfunction "PA1_11") (pintype "bidirectional"))
    )
    (net (code "36") (name "/PA2") (class "Default")
      (node (ref "S3") (pin "2") (pinfunction "2_2") (pintype "bidirectional"))
      (node (ref "T3") (pin "P$1") (pinfunction "P$1_P$1") (pintype "bidirectional"))
      (node (ref "U1") (pin "12") (pinfunction "PA2_12") (pintype "bidirectional"))
    )
    (net (code "37") (name "/RESET") (class "Default")
      (node (ref "J9") (pin "6") (pinfunction "6_6") (pintype "bidirectional"))
      (node (ref "K-1") (pin "1") (pinfunction "1_1") (pintype "bidirectional"))
      (node (ref "R39") (pin "1") (pinfunction "1_1") (pintype "bidirectional"))
      (node (ref "U1") (pin "43") (pinfunction "PB7_43") (pintype "bidirectional"))
    )
    (net (code "38") (name "/RTS{slash}P05") (class "Default")
      (node (ref "S1") (pin "1") (pinfunction "1_1") (pintype "bidirectional"))
      (node (ref "T1") (pin "P$2") (pinfunction "P$2_P$2") (pintype "bidirectional"))
      (node (ref "U11") (pin "20") (pinfunction "P05_20") (pintype "bidirectional"))
    )
    (net (code "39") (name "/RX") (class "Default")
      (node (ref "R16") (pin "2") (pinfunction "2_2") (pintype "bidirectional"))
      (node (ref "RX") (pin "2") (pinfunction "K_2") (pintype "bidirectional"))
    )
    (net (code "40") (name "/RXD{slash}P08") (class "Default")
      (node (ref "S3") (pin "1") (pinfunction "1_1") (pintype "bidirectional"))
      (node (ref "T3") (pin "P$2") (pinfunction "P$2_P$2") (pintype "bidirectional"))
      (node (ref "U11") (pin "23") (pinfunction "P08_23") (pintype "bidirectional"))
    )
    (net (code "41") (name "/SCLK") (class "Default")
      (node (ref "R13") (pin "1") (pinfunction "1_1") (pintype "bidirectional"))
      (node (ref "S5") (pin "1") (pinfunction "1_1") (pintype "bidirectional"))
      (node (ref "S5") (pin "2") (pinfunction "2_2") (pintype "bidirectional"))
      (node (ref "T5") (pin "P$1") (pinfunction "P$1_P$1") (pintype "bidirectional"))
      (node (ref "T5") (pin "P$2") (pinfunction "P$2_P$2") (pintype "bidirectional"))
      (node (ref "U11") (pin "38") (pinfunction "SCLK_38") (pintype "bidirectional"))
    )
    (net (code "42") (name "/SDIO") (class "Default")
      (node (ref "R12") (pin "1") (pinfunction "1_1") (pintype "bidirectional"))
      (node (ref "S6") (pin "1") (pinfunction "1_1") (pintype "bidirectional"))
      (node (ref "S6") (pin "2") (pinfunction "2_2") (pintype "bidirectional"))
      (node (ref "T6") (pin "P$1") (pinfunction "P$1_P$1") (pintype "bidirectional"))
      (node (ref "T6") (pin "P$2") (pinfunction "P$2_P$2") (pintype "bidirectional"))
      (node (ref "U11") (pin "39") (pinfunction "SDIO_39") (pintype "bidirectional"))
    )
    (net (code "43") (name "/STM_JTCK") (class "Default")
      (node (ref "JTCK") (pin "P$1") (pinfunction "1_P$1") (pintype "bidirectional"))
      (node (ref "U1") (pin "37") (pinfunction "PA14_37") (pintype "bidirectional"))
    )
    (net (code "44") (name "/STM_JTMS") (class "Default")
      (node (ref "JTMS") (pin "P$1") (pinfunction "1_P$1") (pintype "bidirectional"))
      (node (ref "U1") (pin "34") (pinfunction "PA13_34") (pintype "bidirectional"))
    )
    (net (code "45") (name "/SWDCLK") (class "Default")
      (node (ref "R13") (pin "2") (pinfunction "2_2") (pintype "bidirectional"))
      (node (ref "U1") (pin "26") (pinfunction "PB13_26") (pintype "bidirectional"))
    )
    (net (code "46") (name "/SWDIO") (class "Default")
      (node (ref "R12") (pin "2") (pinfunction "2_2") (pintype "bidirectional"))
      (node (ref "R14") (pin "1") (pinfunction "1_1") (pintype "bidirectional"))
      (node (ref "U1") (pin "27") (pinfunction "PB14_27") (pintype "bidirectional"))
    )
    (net (code "47") (name "/TX") (class "Default")
      (node (ref "R15") (pin "2") (pinfunction "2_2") (pintype "bidirectional"))
      (node (ref "TX") (pin "2") (pinfunction "K_2") (pintype "bidirectional"))
    )
    (net (code "48") (name "/TXD{slash}P06") (class "Default")
      (node (ref "S4") (pin "1") (pinfunction "1_1") (pintype "bidirectional"))
      (node (ref "T4") (pin "P$2") (pinfunction "P$2_P$2") (pintype "bidirectional"))
      (node (ref "U11") (pin "21") (pinfunction "P06_21") (pintype "bidirectional"))
    )
    (net (code "49") (name "/USB5V") (class "Default")
      (node (ref "Q7") (pin "3") (pinfunction "3_3") (pintype "bidirectional"))
      (node (ref "R21") (pin "2") (pinfunction "2_2") (pintype "bidirectional"))
      (node (ref "R40") (pin "2") (pinfunction "2_2") (pintype "bidirectional"))
      (node (ref "RES1") (pin "2") (pinfunction "2_2") (pintype "bidirectional"))
    )
    (net (code "50") (name "/USBPON") (class "Default")
      (node (ref "Q7") (pin "1") (pinfunction "1_1") (pintype "bidirectional"))
      (node (ref "R24") (pin "1") (pinfunction "1_1") (pintype "bidirectional"))
      (node (ref "U$19") (pin "1") (pinfunction "OUTA_1") (pintype "bidirectional"))
    )
    (net (code "51") (name "/USB_RENUMN") (class "Default")
      (node (ref "R23") (pin "2") (pinfunction "2_2") (pintype "bidirectional"))
      (node (ref "U1") (pin "38") (pinfunction "PA15_38") (pintype "bidirectional"))
    )
    (net (code "52") (name "/VIN") (class "Default")
      (node (ref "C24") (pin "2") (pinfunction "2_2") (pintype "bidirectional"))
      (node (ref "IN5819") (pin "1") (pinfunction "P$1_1") (pintype "bidirectional"))
      (node (ref "J5") (pin "P$1") (pinfunction "VIN_P$1") (pintype "bidirectional"))
      (node (ref "J9") (pin "1") (pinfunction "1_1") (pintype "bidirectional"))
      (node (ref "R25") (pin "1") (pinfunction "1_1") (pintype "bidirectional"))
      (node (ref "R26") (pin "1") (pinfunction "1_1") (pintype "bidirectional"))
      (node (ref "R35") (pin "1") (pinfunction "1_1") (pintype "bidirectional"))
    )
    (net (code "53") (name "/VIN+") (class "Default")
      (node (ref "C41") (pin "1") (pinfunction "1_1") (pintype "bidirectional"))
      (node (ref "IN5819") (pin "2") (pinfunction "P$2_2") (pintype "bidirectional"))
      (node (ref "MP2359") (pin "5") (pinfunction "IN_5") (pintype "bidirectional"))
      (node (ref "R28") (pin "1") (pinfunction "1_1") (pintype "bidirectional"))
      (node (ref "R29") (pin "1") (pinfunction "1_1") (pintype "bidirectional"))
    )
    (net (code "54") (name "AGND") (class "Default")
      (node (ref "A") (pin "4") (pinfunction "4_4") (pintype "bidirectional"))
      (node (ref "B") (pin "4") (pinfunction "4_4") (pintype "bidirectional"))
      (node (ref "BAT") (pin "P$2") (pinfunction "-_P$2") (pintype "bidirectional"))
      (node (ref "C1") (pin "1") (pinfunction "1_1") (pintype "bidirectional"))
      (node (ref "C10") (pin "2") (pinfunction "2_2") (pintype "bidirectional"))
      (node (ref "C11") (pin "2") (pinfunction "2_2") (pintype "bidirectional"))
      (node (ref "C12") (pin "1") (pinfunction "1_1") (pintype "bidirectional"))
      (node (ref "C13") (pin "1") (pinfunction "1_1") (pintype "bidirectional"))
      (node (ref "C14") (pin "2") (pinfunction "2_2") (pintype "bidirectional"))
      (node (ref "C15") (pin "1") (pinfunction "1_1") (pintype "bidirectional"))
      (node (ref "C16") (pin "2") (pinfunction "2_2") (pintype "bidirectional"))
      (node (ref "C17") (pin "2") (pinfunction "2_2") (pintype "bidirectional"))
      (node (ref "C18") (pin "1") (pinfunction "1_1") (pintype "bidirectional"))
      (node (ref "C2") (pin "2") (pinfunction "2_2") (pintype "bidirectional"))
      (node (ref "C20") (pin "1") (pinfunction "1_1") (pintype "bidirectional"))
      (node (ref "C21") (pin "1") (pinfunction "1_1") (pintype "bidirectional"))
      (node (ref "C22") (pin "1") (pinfunction "1_1") (pintype "bidirectional"))
      (node (ref "C23") (pin "2") (pinfunction "2_2") (pintype "bidirectional"))
      (node (ref "C24") (pin "1") (pinfunction "1_1") (pintype "bidirectional"))
      (node (ref "C25") (pin "2") (pinfunction "2_2") (pintype "bidirectional"))
      (node (ref "C26") (pin "1") (pinfunction "1_1") (pintype "bidirectional"))
      (node (ref "C3") (pin "1") (pinfunction "1_1") (pintype "bidirectional"))
      (node (ref "C4") (pin "2") (pinfunction "2_2") (pintype "bidirectional"))
      (node (ref "C41") (pin "2") (pinfunction "2_2") (pintype "bidirectional"))
      (node (ref "C5") (pin "1") (pinfunction "1_1") (pintype "bidirectional"))
      (node (ref "C6") (pin "2") (pinfunction "2_2") (pintype "bidirectional"))
      (node (ref "C7") (pin "2") (pinfunction "2_2") (pintype "bidirectional"))
      (node (ref "C8") (pin "1") (pinfunction "1_1") (pintype "bidirectional"))
      (node (ref "C9") (pin "1") (pinfunction "1_1") (pintype "bidirectional"))
      (node (ref "D3") (pin "1") (pinfunction "P$1_1") (pintype "bidirectional"))
      (node (ref "HEAD-2*1") (pin "1") (pinfunction "1_1") (pintype "bidirectional"))
      (node (ref "J5") (pin "P$2") (pinfunction "GND_P$2") (pintype "bidirectional"))
      (node (ref "J5") (pin "P$3") (pinfunction "DET_P$3") (pintype "bidirectional"))
      (node (ref "J8") (pin "7") (pinfunction "7_7") (pintype "bidirectional"))
      (node (ref "J9") (pin "2") (pinfunction "2_2") (pintype "bidirectional"))
      (node (ref "J9") (pin "3") (pinfunction "3_3") (pintype "bidirectional"))
      (node (ref "K-1") (pin "2") (pinfunction "2_2") (pintype "bidirectional"))
      (node (ref "MP2359") (pin "2") (pinfunction "GND_2") (pintype "bidirectional"))
      (node (ref "NMOS2") (pin "2") (pinfunction "3_2") (pintype "bidirectional"))
      (node (ref "NMOS3") (pin "2") (pinfunction "3_2") (pintype "bidirectional"))
      (node (ref "R17") (pin "2") (pinfunction "2_2") (pintype "bidirectional"))
      (node (ref "R22") (pin "1") (pinfunction "1_1") (pintype "bidirectional"))
      (node (ref "R26") (pin "2") (pinfunction "2_2") (pintype "bidirectional"))
      (node (ref "R27") (pin "2") (pinfunction "2_2") (pintype "bidirectional"))
      (node (ref "R32") (pin "2") (pinfunction "2_2") (pintype "bidirectional"))
      (node (ref "R33") (pin "2") (pinfunction "2_2") (pintype "bidirectional"))
      (node (ref "R36") (pin "1") (pinfunction "1_1") (pintype "bidirectional"))
      (node (ref "R38") (pin "1") (pinfunction "1_1") (pintype "bidirectional"))
      (node (ref "R40") (pin "1") (pinfunction "1_1") (pintype "bidirectional"))
      (node (ref "R6") (pin "1") (pinfunction "1_1") (pintype "bidirectional"))
      (node (ref "R7") (pin "1") (pinfunction "1_1") (pintype "bidirectional"))
      (node (ref "R8") (pin "1") (pinfunction "1_1") (pintype "bidirectional"))
      (node (ref "U$15") (pin "4") (pinfunction "ID_4") (pintype "bidirectional"))
      (node (ref "U$15") (pin "5") (pinfunction "GND3_5") (pintype "bidirectional"))
      (node (ref "U$15") (pin "6") (pinfunction "GND_6") (pintype "bidirectional"))
      (node (ref "U$15") (pin "7") (pinfunction "GND1_7") (pintype "bidirectional"))
      (node (ref "U$15") (pin "8") (pinfunction "GND4_8") (pintype "bidirectional"))
      (node (ref "U$15") (pin "9") (pinfunction "GND5_9") (pintype "bidirectional"))
      (node (ref "U$16") (pin "1") (pinfunction "VSS_1") (pintype "power_in"))
      (node (ref "U$19") (pin "4") (pinfunction "VSS_4") (pintype "bidirectional"))
      (node (ref "U$2") (pin "2") (pinfunction "2_2") (pintype "passive"))
      (node (ref "U$2") (pin "3") (pinfunction "3_3") (pintype "passive"))
      (node (ref "U$3") (pin "1") (pinfunction "GND_1") (pintype "bidirectional"))
      (node (ref "U$3") (pin "9") (pinfunction "GND1_9") (pintype "bidirectional"))
      (node (ref "U1") (pin "23") (pinfunction "VSS1_23") (pintype "bidirectional"))
      (node (ref "U1") (pin "35") (pinfunction "VSS2_35") (pintype "bidirectional"))
      (node (ref "U1") (pin "47") (pinfunction "VSS3_47") (pintype "bidirectional"))
      (node (ref "U1") (pin "8") (pinfunction "VSSA_8") (pintype "bidirectional"))
      (node (ref "U11") (pin "1") (pinfunction "GND1_1") (pintype "bidirectional"))
      (node (ref "U11") (pin "14") (pinfunction "GND7_14") (pintype "bidirectional"))
      (node (ref "U11") (pin "2") (pinfunction "GND2_2") (pintype "bidirectional"))
      (node (ref "U11") (pin "26") (pinfunction "GND3_26") (pintype "bidirectional"))
      (node (ref "U11") (pin "43") (pinfunction "GND5_43") (pintype "bidirectional"))
      (node (ref "Y1") (pin "2") (pinfunction "2_2") (pintype "bidirectional"))
      (node (ref "Y1") (pin "4") (pinfunction "4_4") (pintype "bidirectional"))
    )
    (net (code "55") (name "Net-(BAT-+)") (class "Default")
      (node (ref "BAT") (pin "P$1") (pinfunction "+_P$1") (pintype "bidirectional"))
      (node (ref "BT-VDD") (pin "1") (pinfunction "1_1") (pintype "bidirectional"))
      (node (ref "L20") (pin "2") (pinfunction "2_2") (pintype "bidirectional"))
      (node (ref "S55") (pin "P$1") (pinfunction "P$1_P$1") (pintype "bidirectional"))
    )
    (net (code "56") (name "Net-(C5-Pad2)") (class "Default")
      (node (ref "C5") (pin "2") (pinfunction "2_2") (pintype "bidirectional"))
      (node (ref "NFC") (pin "2") (pinfunction "2_2") (pintype "bidirectional"))
      (node (ref "NFC") (pin "3") (pinfunction "3_3") (pintype "bidirectional"))
      (node (ref "R3") (pin "2") (pinfunction "2_2") (pintype "bidirectional"))
    )
    (net (code "57") (name "Net-(C6-Pad1)") (class "Default")
      (node (ref "C6") (pin "1") (pinfunction "1_1") (pintype "bidirectional"))
      (node (ref "NFC") (pin "1") (pinfunction "1_1") (pintype "bidirectional"))
      (node (ref "R1") (pin "2") (pinfunction "2_2") (pintype "bidirectional"))
    )
    (net (code "58") (name "Net-(D1-A)") (class "Default")
      (node (ref "D1") (pin "1") (pinfunction "A_1") (pintype "bidirectional"))
      (node (ref "U$19") (pin "6") (pinfunction "-INB_6") (pintype "bidirectional"))
      (node (ref "U$19") (pin "7") (pinfunction "OUTB_7") (pintype "bidirectional"))
    )
    (net (code "59") (name "Net-(D1-K)") (class "Default")
      (node (ref "D1") (pin "2") (pinfunction "K_2") (pintype "bidirectional"))
      (node (ref "R38") (pin "2") (pinfunction "2_2") (pintype "bidirectional"))
    )
    (net (code "60") (name "Net-(D3-P$2)") (class "Default")
      (node (ref "C19") (pin "2") (pinfunction "2_2") (pintype "bidirectional"))
      (node (ref "D3") (pin "2") (pinfunction "P$2_2") (pintype "bidirectional"))
      (node (ref "L3") (pin "P$1") (pinfunction "1_P$1") (pintype "bidirectional"))
      (node (ref "MP2359") (pin "6") (pinfunction "SW_6") (pintype "bidirectional"))
    )
    (net (code "61") (name "Net-(D4-K)") (class "Default")
      (node (ref "D4") (pin "2") (pinfunction "K_2") (pintype "bidirectional"))
      (node (ref "R33") (pin "1") (pinfunction "1_1") (pintype "bidirectional"))
    )
    (net (code "62") (name "Net-(HEAD-2*1-Pad6)") (class "Default")
      (node (ref "HEAD-2*1") (pin "6") (pinfunction "6_6") (pintype "bidirectional"))
      (node (ref "R39") (pin "2") (pinfunction "2_2") (pintype "bidirectional"))
    )
    (net (code "63") (name "Net-(L1-Pad1)") (class "Default")
      (node (ref "L1") (pin "1") (pinfunction "1_1") (pintype "bidirectional"))
      (node (ref "L2") (pin "2") (pinfunction "2_2") (pintype "bidirectional"))
    )
    (net (code "64") (name "Net-(MP2359-BST)") (class "Default")
      (node (ref "C19") (pin "1") (pinfunction "1_1") (pintype "bidirectional"))
      (node (ref "MP2359") (pin "1") (pinfunction "BST_1") (pintype "bidirectional"))
    )
    (net (code "65") (name "Net-(MP2359-EN)") (class "Default")
      (node (ref "MP2359") (pin "4") (pinfunction "EN_4") (pintype "bidirectional"))
      (node (ref "NMOS2") (pin "3") (pinfunction "2_3") (pintype "bidirectional"))
      (node (ref "R29") (pin "2") (pinfunction "2_2") (pintype "bidirectional"))
    )
    (net (code "66") (name "Net-(MP2359-FB)") (class "Default")
      (node (ref "MP2359") (pin "3") (pinfunction "FB_3") (pintype "bidirectional"))
      (node (ref "R31") (pin "2") (pinfunction "2_2") (pintype "bidirectional"))
      (node (ref "R32") (pin "1") (pinfunction "1_1") (pintype "bidirectional"))
    )
    (net (code "67") (name "Net-(NMOS3-2)") (class "Default")
      (node (ref "NMOS2") (pin "1") (pinfunction "1_1") (pintype "bidirectional"))
      (node (ref "NMOS3") (pin "3") (pinfunction "2_3") (pintype "bidirectional"))
      (node (ref "R28") (pin "2") (pinfunction "2_2") (pintype "bidirectional"))
    )
    (net (code "68") (name "Net-(NMOS3-Pad1)") (class "Default")
      (node (ref "NMOS3") (pin "1") (pinfunction "1_1") (pintype "bidirectional"))
      (node (ref "R25") (pin "2") (pinfunction "2_2") (pintype "bidirectional"))
      (node (ref "R27") (pin "1") (pinfunction "1_1") (pintype "bidirectional"))
    )
    (net (code "69") (name "Net-(Q4-3)") (class "Default")
      (node (ref "Q4") (pin "2") (pinfunction "3_2") (pintype "bidirectional"))
      (node (ref "R18") (pin "2") (pinfunction "2_2") (pintype "bidirectional"))
    )
    (net (code "70") (name "Net-(Q4-Pad1)") (class "Default")
      (node (ref "Q4") (pin "1") (pinfunction "1_1") (pintype "bidirectional"))
      (node (ref "R21") (pin "1") (pinfunction "1_1") (pintype "bidirectional"))
      (node (ref "R22") (pin "2") (pinfunction "2_2") (pintype "bidirectional"))
      (node (ref "R23") (pin "1") (pinfunction "1_1") (pintype "bidirectional"))
    )
    (net (code "71") (name "Net-(R30-Pad2)") (class "Default")
      (node (ref "R30") (pin "2") (pinfunction "2_2") (pintype "bidirectional"))
      (node (ref "R31") (pin "1") (pinfunction "1_1") (pintype "bidirectional"))
    )
    (net (code "72") (name "Net-(TP1-1)") (class "Default")
      (node (ref "R10") (pin "2") (pinfunction "2_2") (pintype "bidirectional"))
      (node (ref "TP1") (pin "P$1") (pinfunction "1_P$1") (pintype "bidirectional"))
      (node (ref "U1") (pin "21") (pinfunction "PB10_21") (pintype "bidirectional"))
    )
    (net (code "73") (name "Net-(TP2-1)") (class "Default")
      (node (ref "R11") (pin "2") (pinfunction "2_2") (pintype "bidirectional"))
      (node (ref "TP2") (pin "P$1") (pinfunction "1_P$1") (pintype "bidirectional"))
      (node (ref "U1") (pin "22") (pinfunction "PB11_22") (pintype "bidirectional"))
    )
    (net (code "74") (name "Net-(U$3-RST)") (class "Default")
      (node (ref "R5") (pin "1") (pinfunction "1_1") (pintype "bidirectional"))
      (node (ref "R6") (pin "2") (pinfunction "2_2") (pintype "bidirectional"))
      (node (ref "U$3") (pin "7") (pinfunction "RST_7") (pintype "bidirectional"))
    )
    (net (code "75") (name "Net-(U$15-D+)") (class "Default")
      (node (ref "R18") (pin "1") (pinfunction "1_1") (pintype "bidirectional"))
      (node (ref "R19") (pin "1") (pinfunction "1_1") (pintype "bidirectional"))
      (node (ref "U$15") (pin "3") (pinfunction "D+_3") (pintype "bidirectional"))
    )
    (net (code "76") (name "Net-(U$15-D-)") (class "Default")
      (node (ref "R20") (pin "1") (pinfunction "1_1") (pintype "bidirectional"))
      (node (ref "U$15") (pin "2") (pinfunction "D-_2") (pintype "bidirectional"))
    )
    (net (code "77") (name "Net-(U$15-VBUS)") (class "Default")
      (node (ref "RES1") (pin "1") (pinfunction "1_1") (pintype "bidirectional"))
      (node (ref "U$15") (pin "1") (pinfunction "VBUS_1") (pintype "bidirectional"))
    )
    (net (code "78") (name "Net-(U$19-+INA)") (class "Default")
      (node (ref "R35") (pin "2") (pinfunction "2_2") (pintype "bidirectional"))
      (node (ref "R36") (pin "2") (pinfunction "2_2") (pintype "bidirectional"))
      (node (ref "U$19") (pin "3") (pinfunction "+INA_3") (pintype "bidirectional"))
    )
    (net (code "79") (name "Net-(U$19-+INB)") (class "Default")
      (node (ref "R37") (pin "2") (pinfunction "2_2") (pintype "bidirectional"))
      (node (ref "U$19") (pin "5") (pinfunction "+INB_5") (pintype "bidirectional"))
    )
    (net (code "80") (name "Net-(U$19--INA)") (class "Default")
      (node (ref "R34") (pin "2") (pinfunction "2_2") (pintype "bidirectional"))
      (node (ref "U$19") (pin "2") (pinfunction "-INA_2") (pintype "bidirectional"))
    )
    (net (code "81") (name "Net-(U1-BOOT0)") (class "Default")
      (node (ref "R17") (pin "1") (pinfunction "1_1") (pintype "bidirectional"))
      (node (ref "U1") (pin "44") (pinfunction "BOOT0_44") (pintype "bidirectional"))
    )
    (net (code "82") (name "Net-(U1-PA3)") (class "Default")
      (node (ref "S4") (pin "2") (pinfunction "2_2") (pintype "bidirectional"))
      (node (ref "T4") (pin "P$1") (pinfunction "P$1_P$1") (pintype "bidirectional"))
      (node (ref "U1") (pin "13") (pinfunction "PA3_13") (pintype "bidirectional"))
    )
    (net (code "83") (name "Net-(U1-PB5)") (class "Default")
      (node (ref "R15") (pin "1") (pinfunction "1_1") (pintype "bidirectional"))
      (node (ref "U1") (pin "41") (pinfunction "PB5_41") (pintype "bidirectional"))
    )
    (net (code "84") (name "Net-(U1-PB6)") (class "Default")
      (node (ref "R16") (pin "1") (pinfunction "1_1") (pintype "bidirectional"))
      (node (ref "U1") (pin "42") (pinfunction "PB6_42") (pintype "bidirectional"))
    )
    (net (code "85") (name "Net-(U1-PB12)") (class "Default")
      (node (ref "R14") (pin "2") (pinfunction "2_2") (pintype "bidirectional"))
      (node (ref "U1") (pin "25") (pinfunction "PB12_25") (pintype "bidirectional"))
    )
    (net (code "86") (name "Net-(U1-PC13)") (class "Default")
      (node (ref "R7") (pin "2") (pinfunction "2_2") (pintype "bidirectional"))
      (node (ref "U1") (pin "2") (pinfunction "PC13_2") (pintype "bidirectional"))
    )
    (net (code "87") (name "Net-(U1-PC14{slash}OSC32_IN)") (class "Default")
      (node (ref "R8") (pin "2") (pinfunction "2_2") (pintype "bidirectional"))
      (node (ref "U1") (pin "3") (pinfunction "PC14/OSC32_IN_3") (pintype "bidirectional"))
    )
    (net (code "88") (name "Net-(U1-PD0{slash}OSC_IN)") (class "Default")
      (node (ref "C11") (pin "1") (pinfunction "1_1") (pintype "bidirectional"))
      (node (ref "U1") (pin "5") (pinfunction "PD0/OSC_IN_5") (pintype "bidirectional"))
      (node (ref "Y1") (pin "3") (pinfunction "3_3") (pintype "bidirectional"))
    )
    (net (code "89") (name "Net-(U1-PD1{slash}OSC_OUT)") (class "Default")
      (node (ref "C12") (pin "2") (pinfunction "2_2") (pintype "bidirectional"))
      (node (ref "U1") (pin "6") (pinfunction "PD1/OSC_OUT_6") (pintype "bidirectional"))
      (node (ref "Y1") (pin "1") (pinfunction "1_1") (pintype "bidirectional"))
    )
    (net (code "90") (name "Net-(U11-DCC)") (class "Default")
      (node (ref "L1") (pin "2") (pinfunction "2_2") (pintype "bidirectional"))
      (node (ref "U11") (pin "12") (pinfunction "DCC_12") (pintype "bidirectional"))
    )
    (net (code "91") (name "Net-(U11-DEC4)") (class "Default")
      (node (ref "C1") (pin "2") (pinfunction "2_2") (pintype "bidirectional"))
      (node (ref "L2") (pin "1") (pinfunction "1_1") (pintype "bidirectional"))
      (node (ref "U11") (pin "11") (pinfunction "DEC4_11") (pintype "bidirectional"))
    )
    (net (code "92") (name "Net-(U11-P00)") (class "Default")
      (node (ref "C3") (pin "2") (pinfunction "2_2") (pintype "bidirectional"))
      (node (ref "U$2") (pin "1") (pinfunction "1_1") (pintype "passive"))
      (node (ref "U11") (pin "15") (pinfunction "P00_15") (pintype "bidirectional"))
    )
    (net (code "93") (name "Net-(U11-P01)") (class "Default")
      (node (ref "C4") (pin "1") (pinfunction "1_1") (pintype "bidirectional"))
      (node (ref "U$2") (pin "4") (pinfunction "4_4") (pintype "passive"))
      (node (ref "U11") (pin "16") (pinfunction "P01_16") (pintype "bidirectional"))
    )
    (net (code "94") (name "VCC") (class "Default")
      (node (ref "C2") (pin "1") (pinfunction "1_1") (pintype "bidirectional"))
      (node (ref "C23") (pin "1") (pinfunction "1_1") (pintype "bidirectional"))
      (node (ref "C7") (pin "1") (pinfunction "1_1") (pintype "bidirectional"))
      (node (ref "L20") (pin "1") (pinfunction "1_1") (pintype "bidirectional"))
      (node (ref "U11") (pin "13") (pinfunction "VDD1_13") (pintype "bidirectional"))
      (node (ref "U11") (pin "3") (pinfunction "VDD_3") (pintype "bidirectional"))
    )
    (net (code "95") (name "unconnected-(U$3-NC1-Pad3)") (class "Default")
      (node (ref "U$3") (pin "3") (pinfunction "NC1_3") (pintype "bidirectional"))
    )
    (net (code "96") (name "unconnected-(U$3-NC2-Pad4)") (class "Default")
      (node (ref "U$3") (pin "4") (pinfunction "NC2_4") (pintype "bidirectional"))
    )
    (net (code "97") (name "unconnected-(U$3-NC3-Pad5)") (class "Default")
      (node (ref "U$3") (pin "5") (pinfunction "NC3_5") (pintype "bidirectional"))
    )
    (net (code "98") (name "unconnected-(U1-PA4-Pad14)") (class "Default")
      (node (ref "U1") (pin "14") (pinfunction "PA4_14") (pintype "bidirectional"))
    )
    (net (code "99") (name "unconnected-(U1-PA5-Pad15)") (class "Default")
      (node (ref "U1") (pin "15") (pinfunction "PA5_15") (pintype "bidirectional"))
    )
    (net (code "100") (name "unconnected-(U1-PA6-Pad16)") (class "Default")
      (node (ref "U1") (pin "16") (pinfunction "PA6_16") (pintype "bidirectional"))
    )
    (net (code "101") (name "unconnected-(U1-PA7-Pad17)") (class "Default")
      (node (ref "U1") (pin "17") (pinfunction "PA7_17") (pintype "bidirectional"))
    )
    (net (code "102") (name "unconnected-(U1-PA8-Pad29)") (class "Default")
      (node (ref "U1") (pin "29") (pinfunction "PA8_29") (pintype "bidirectional"))
    )
    (net (code "103") (name "unconnected-(U1-PA9-Pad30)") (class "Default")
      (node (ref "U1") (pin "30") (pinfunction "PA9_30") (pintype "bidirectional"))
    )
    (net (code "104") (name "unconnected-(U1-PA10-Pad31)") (class "Default")
      (node (ref "U1") (pin "31") (pinfunction "PA10_31") (pintype "bidirectional"))
    )
    (net (code "105") (name "unconnected-(U1-PB0-Pad18)") (class "Default")
      (node (ref "U1") (pin "18") (pinfunction "PB0_18") (pintype "bidirectional"))
    )
    (net (code "106") (name "unconnected-(U1-PB1-Pad19)") (class "Default")
      (node (ref "U1") (pin "19") (pinfunction "PB1_19") (pintype "bidirectional"))
    )
    (net (code "107") (name "unconnected-(U1-PB2-Pad20)") (class "Default")
      (node (ref "U1") (pin "20") (pinfunction "PB2_20") (pintype "bidirectional"))
    )
    (net (code "108") (name "unconnected-(U1-PB3-Pad39)") (class "Default")
      (node (ref "U1") (pin "39") (pinfunction "PB3_39") (pintype "bidirectional"))
    )
    (net (code "109") (name "unconnected-(U1-PB4-Pad40)") (class "Default")
      (node (ref "U1") (pin "40") (pinfunction "PB4_40") (pintype "bidirectional"))
    )
    (net (code "110") (name "unconnected-(U1-PB8-Pad45)") (class "Default")
      (node (ref "U1") (pin "45") (pinfunction "PB8_45") (pintype "bidirectional"))
    )
    (net (code "111") (name "unconnected-(U1-PB9-Pad46)") (class "Default")
      (node (ref "U1") (pin "46") (pinfunction "PB9_46") (pintype "bidirectional"))
    )
    (net (code "112") (name "unconnected-(U1-PB15-Pad28)") (class "Default")
      (node (ref "U1") (pin "28") (pinfunction "PB15_28") (pintype "bidirectional"))
    )
    (net (code "113") (name "unconnected-(U1-PC15{slash}OSC32_OUT-Pad4)") (class "Default")
      (node (ref "U1") (pin "4") (pinfunction "PC15/OSC32_OUT_4") (pintype "bidirectional"))
    )
  )
)
